# Connectors.net
KiCad netlist of a schematic drawn in Altium Designer
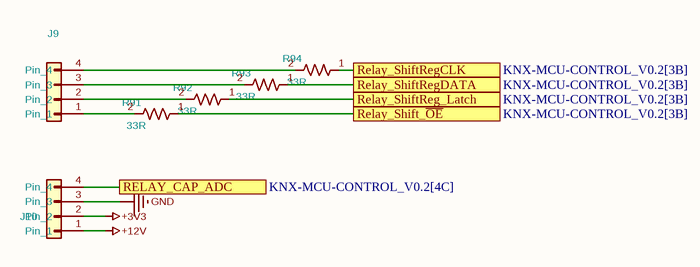
[diagram p0: Connectors.SchDoc]

(export (version "E")
  (design (tool "Eeschema 10.0.6"))
  (components
    (comp (ref "J9")
      (value "DK501-1X6SBT-3X13MM")
      (footprint "PinHeader_1x04_P2.54mm_Vertical")
      (description "PIN HEADER 6PIN(1x6) 2.54mm THT V/T 3X13MM")
      (fields (field (name "MANUFACTURER") "OEM"))
      (libsource (lib "Connector_Generic") (part "Conn_01x04"))
    )
    (comp (ref "J10")
      (value "DK501-1X6SBT-3X13MM")
      (footprint "PinHeader_1x04_P2.54mm_Vertical")
      (description "PIN HEADER 6PIN(1x6) 2.54mm THT V/T 3X13MM")
      (fields (field (name "MANUFACTURER") "OEM"))
      (libsource (lib "Connector_Generic") (part "Conn_01x04"))
    )
    (comp (ref "R91")
      (value "33R")
      (footprint "R_0603_1608Metric")
      (fields
        (field (name "MANUFACTURER PART NUMBER") "RC0603JR-0733RL")
        (field (name "MANUFACTURER") "YAGEO")
      )
      (libsource (lib "Device") (part "R_US"))
    )
    (comp (ref "R92")
      (value "33R")
      (footprint "R_0603_1608Metric")
      (fields
        (field (name "MANUFACTURER PART NUMBER") "RC0603JR-0733RL")
        (field (name "MANUFACTURER") "YAGEO")
      )
      (libsource (lib "Device") (part "R_US"))
    )
    (comp (ref "R93")
      (value "33R")
      (footprint "R_0603_1608Metric")
      (fields
        (field (name "MANUFACTURER PART NUMBER") "RC0603JR-0733RL")
        (field (name "MANUFACTURER") "YAGEO")
      )
      (libsource (lib "Device") (part "R_US"))
    )
    (comp (ref "R94")
      (value "33R")
      (footprint "R_0603_1608Metric")
      (fields
        (field (name "MANUFACTURER PART NUMBER") "RC0603JR-0733RL")
        (field (name "MANUFACTURER") "YAGEO")
      )
      (libsource (lib "Device") (part "R_US"))
    )
  )
  (nets
    (net (code "1") (name "+3V3") (class "Default")
      (node (ref "J10") (pin "2") (pinfunction "Pin_2_2") (pintype "passive"))
    )
    (net (code "2") (name "+12V") (class "Default")
      (node (ref "J10") (pin "1") (pinfunction "Pin_1_1") (pintype "passive"))
    )
    (net (code "3") (name "/RELAY_CAP_ADC") (class "Default")
      (node (ref "J10") (pin "4") (pinfunction "Pin_4_4") (pintype "passive"))
    )
    (net (code "4") (name "/Relay_ShiftRegCLK") (class "Default")
      (node (ref "R94") (pin "1") (pinfunction "1_1") (pintype "passive"))
    )
    (net (code "5") (name "/Relay_ShiftRegDATA") (class "Default")
      (node (ref "R93") (pin "1") (pinfunction "1_1") (pintype "passive"))
    )
    (net (code "6") (name "/Relay_ShiftReg_Latch") (class "Default")
      (node (ref "R92") (pin "1") (pinfunction "1_1") (pintype "passive"))
    )
    (net (code "7") (name "/Relay_Shift_~{OE}") (class "Default")
      (node (ref "R91") (pin "1") (pinfunction "1_1") (pintype "passive"))
    )
    (net (code "8") (name "GND") (class "Default")
      (node (ref "J10") (pin "3") (pinfunction "Pin_3_3") (pintype "passive"))
    )
    (net (code "9") (name "Net-(J9-Pin_1)") (class "Default")
      (node (ref "J9") (pin "1") (pinfunction "Pin_1_1") (pintype "passive"))
      (node (ref "R91") (pin "2") (pinfunction "2_2") (pintype "passive"))
    )
    (net (code "10") (name "Net-(J9-Pin_2)") (class "Default")
      (node (ref "J9") (pin "2") (pinfunction "Pin_2_2") (pintype "passive"))
      (node (ref "R92") (pin "2") (pinfunction "2_2") (pintype "passive"))
    )
    (net (code "11") (name "Net-(J9-Pin_3)") (class "Default")
      (node (ref "J9") (pin "3") (pinfunction "Pin_3_3") (pintype "passive"))
      (node (ref "R93") (pin "2") (pinfunction "2_2") (pintype "passive"))
    )
    (net (code "12") (name "Net-(J9-Pin_4)") (class "Default")
      (node (ref "J9") (pin "4") (pinfunction "Pin_4_4") (pintype "passive"))
      (node (ref "R94") (pin "2") (pinfunction "2_2") (pintype "passive"))
    )
  )
)
